# ATmega_lightSensor_blink.net
KiCad netlist of a schematic drawn in EasyEDA
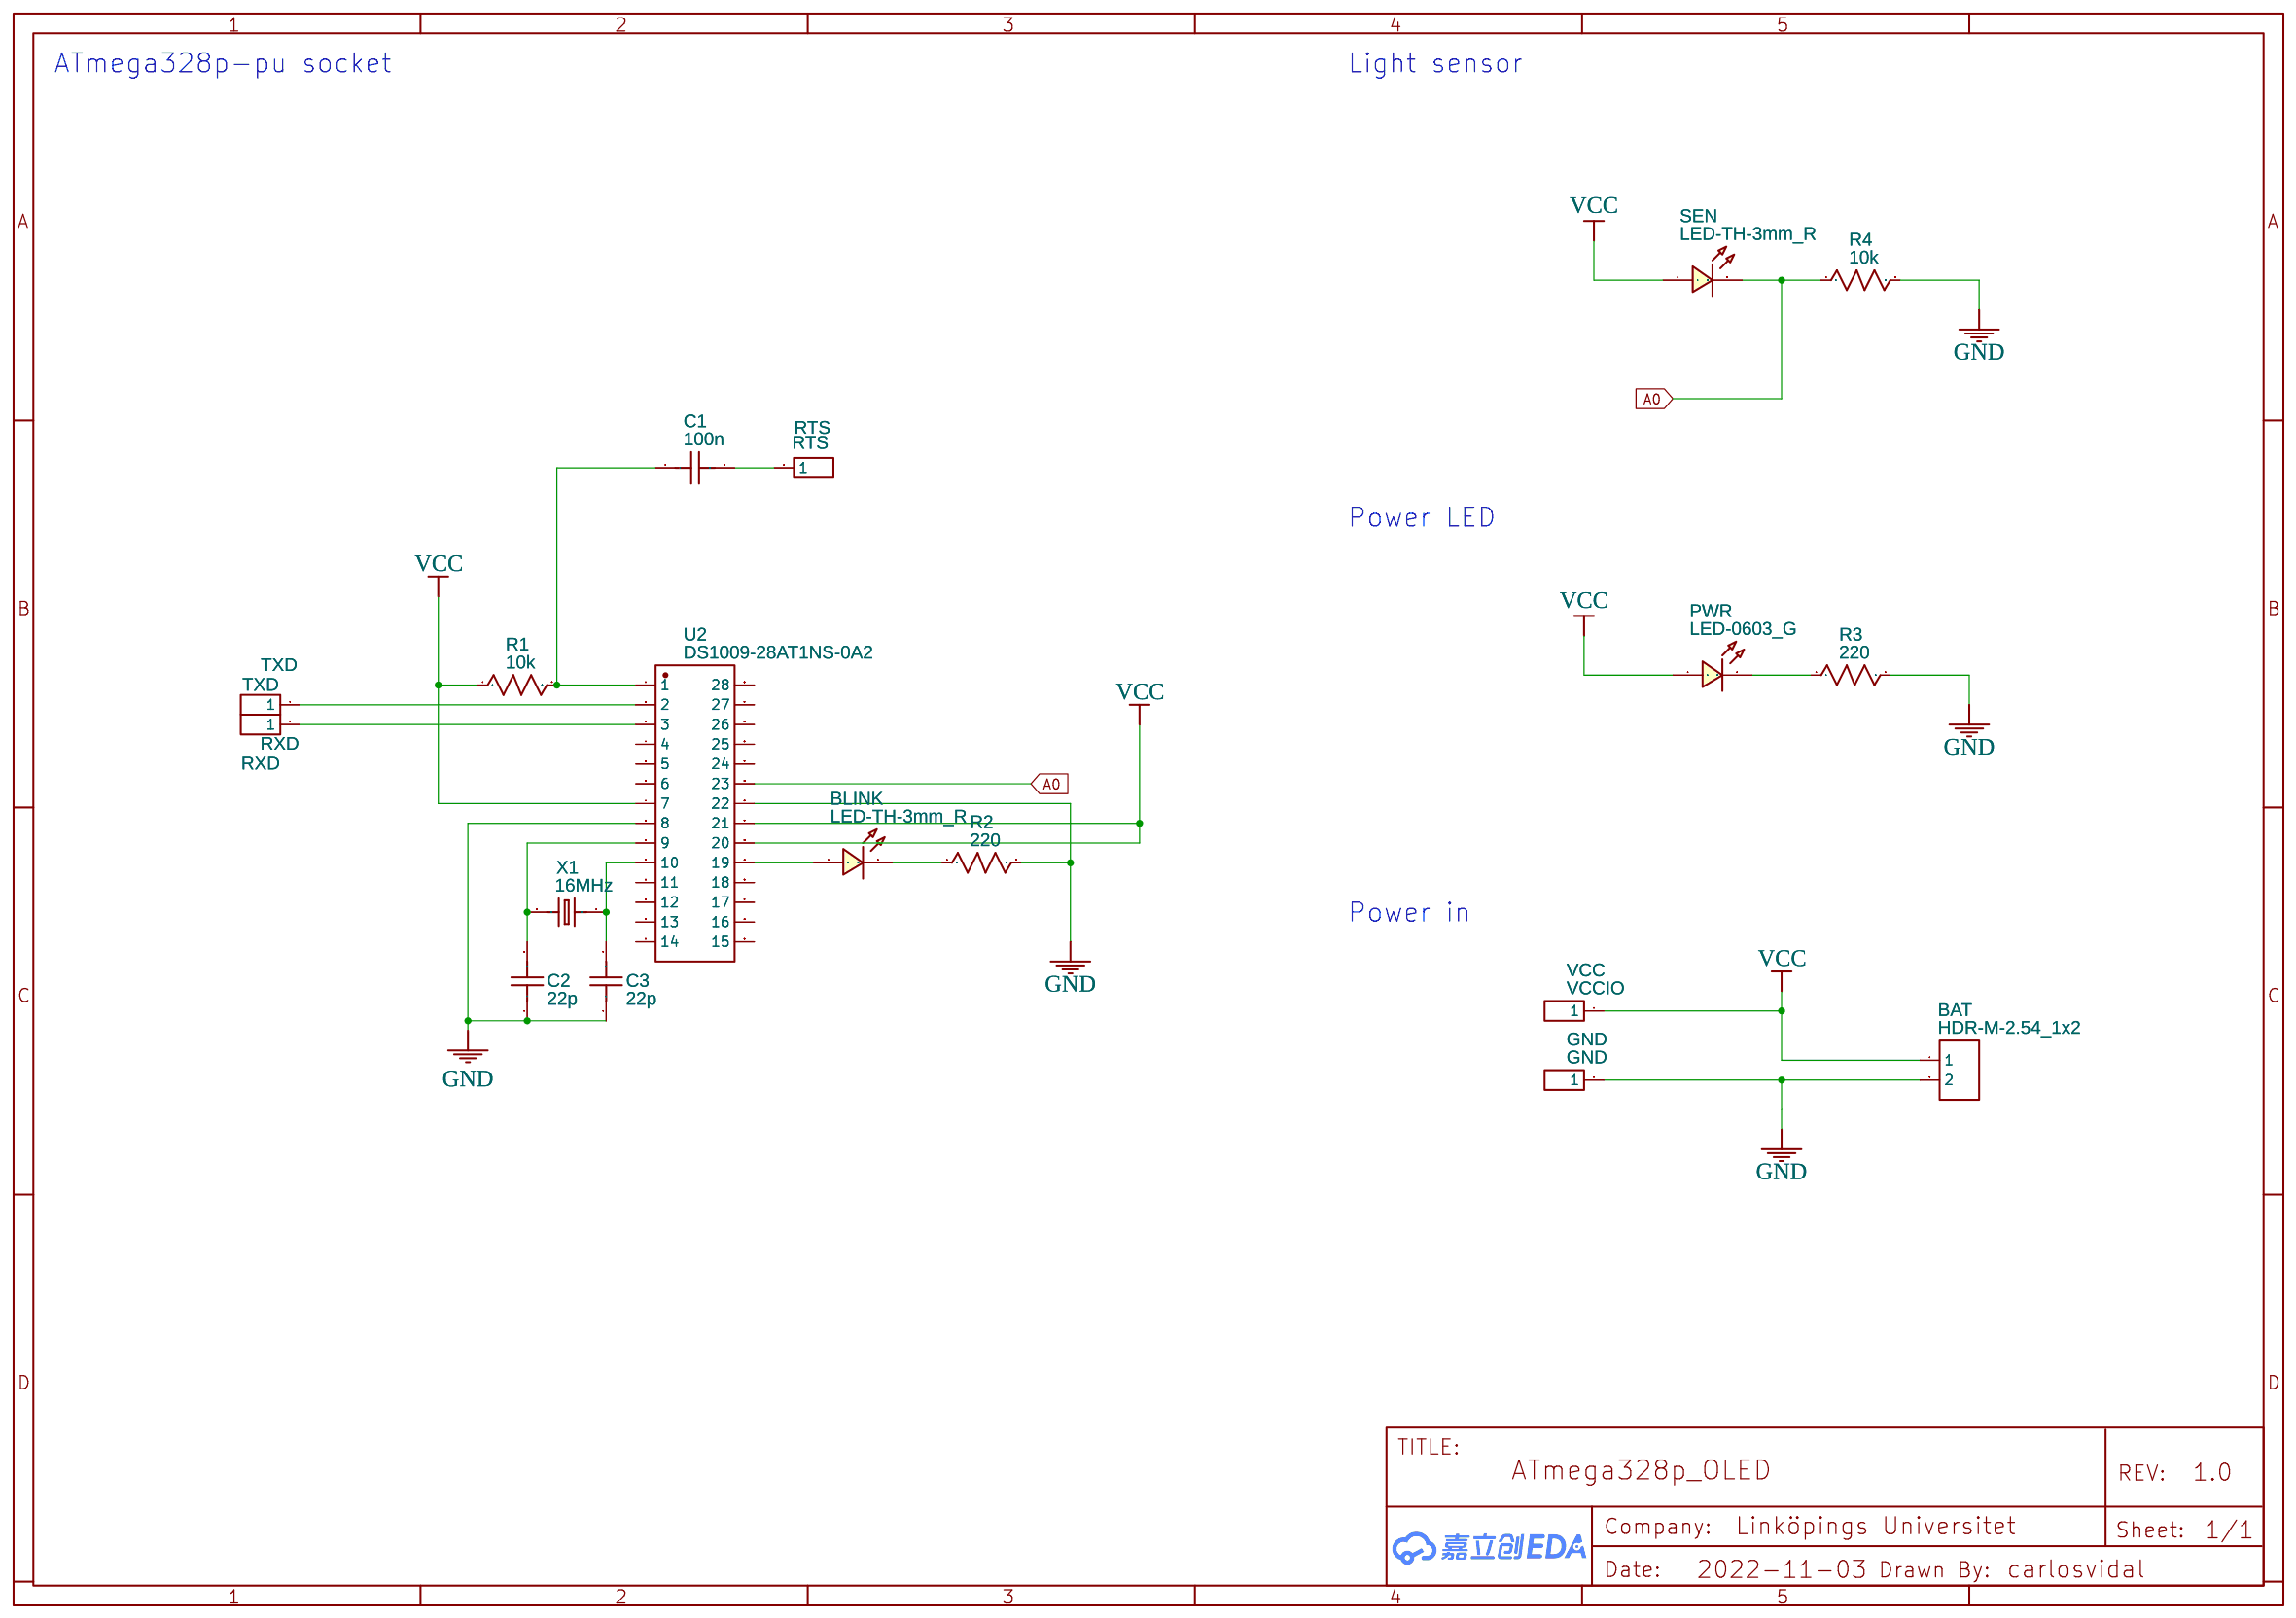
[diagram p0: schematic sheet]

(export (version "E")
  (design (tool "Eeschema 10.0.6"))
  (components
    (comp (ref "BAT") (value "HDR-M-2.54_1x2") (libsource (lib "") (part "HDR-M-2.54_1x2")))
    (comp (ref "BLINK")
      (value "LED-TH-3mm_R")
      (fields
        (field (name "Manufacturer Part") "204-10SDRD/S530-A3-L")
        (field (name "Manufacturer") "EVERLIGHT(台湾亿光)")
      )
      (libsource (lib "") (part "LED-TH-3mm_R"))
    )
    (comp (ref "C1") (value "100n") (libsource (lib "") (part "C_0603_US_1")))
    (comp (ref "C2") (value "22p") (libsource (lib "") (part "C_0603_US")))
    (comp (ref "C3") (value "22p") (libsource (lib "") (part "C_0603_US")))
    (comp (ref "GND") (value "GND") (libsource (lib "") (part "HDR-M-2.54_1x1")))
    (comp (ref "PWR")
      (value "LED-0603_G")
      (fields
        (field (name "Manufacturer Part") "19-217/GHC-YR1S2/3T")
        (field (name "Manufacturer") "EVERLIGHT(台湾亿光)")
      )
      (libsource (lib "") (part "LED-0603_G"))
    )
    (comp (ref "R1") (value "10k") (libsource (lib "") (part "R_0603_US")))
    (comp (ref "R2") (value "220") (libsource (lib "") (part "R_0603_US")))
    (comp (ref "R3") (value "220") (libsource (lib "") (part "R_0603_US")))
    (comp (ref "R4") (value "10k") (libsource (lib "") (part "R_0603_US")))
    (comp (ref "RTS") (value "RTS") (libsource (lib "") (part "HDR-M-2.54_1x1_1")))
    (comp (ref "RXD") (value "RXD") (libsource (lib "") (part "HDR-M-2.54_1x1_3")))
    (comp (ref "SEN")
      (value "LED-TH-3mm_R")
      (fields
        (field (name "Manufacturer Part") "204-10SDRD/S530-A3-L")
        (field (name "Manufacturer") "EVERLIGHT(台湾亿光)")
      )
      (libsource (lib "") (part "LED-TH-3mm_R_1"))
    )
    (comp (ref "TXD") (value "TXD") (libsource (lib "") (part "HDR-M-2.54_1x1_4")))
    (comp (ref "U2")
      (value "DS1009-28AT1NS-0A2")
      (fields (field (name "Manufacturer") "CONNFLY"))
      (libsource (lib "") (part "DS1009-28AT1NS-0A2"))
    )
    (comp (ref "VCC") (value "VCCIO") (libsource (lib "") (part "HDR-M-2.54_1x1_2")))
    (comp (ref "X1")
      (value "16MHz")
      (fields (field (name "Manufacturer Part") "TAXM16M2GLFBET2T") (field (name "Manufacturer") "TAE(雅晶鑫)"))
      (libsource (lib "") (part "HC-49SM16MHz20pF30ppm"))
    )
  )
  (nets
    (net (code "1") (name "A0") (class "Default")
      (node (ref "R4") (pin "1") (pinfunction "1_1") (pintype "unspecified"))
      (node (ref "SEN") (pin "2") (pinfunction "2_2") (pintype "unspecified"))
      (node (ref "U2") (pin "23") (pinfunction "23_23") (pintype "unspecified"))
    )
    (net (code "2") (name "GND") (class "Default")
      (node (ref "BAT") (pin "2") (pinfunction "2_2") (pintype "unspecified"))
      (node (ref "C2") (pin "1") (pinfunction "1_1") (pintype "unspecified"))
      (node (ref "C3") (pin "1") (pinfunction "1_1") (pintype "unspecified"))
      (node (ref "GND") (pin "1") (pinfunction "1_1") (pintype "input"))
      (node (ref "R2") (pin "2") (pinfunction "2_2") (pintype "unspecified"))
      (node (ref "R3") (pin "2") (pinfunction "2_2") (pintype "unspecified"))
      (node (ref "R4") (pin "2") (pinfunction "2_2") (pintype "unspecified"))
      (node (ref "U2") (pin "22") (pinfunction "22_22") (pintype "unspecified"))
      (node (ref "U2") (pin "8") (pinfunction "8_8") (pintype "unspecified"))
    )
    (net (code "3") (name "Net-(BLINK-Pad1)") (class "Default")
      (node (ref "BLINK") (pin "1") (pinfunction "1_1") (pintype "unspecified"))
      (node (ref "U2") (pin "19") (pinfunction "19_19") (pintype "unspecified"))
    )
    (net (code "4") (name "Net-(BLINK-Pad2)") (class "Default")
      (node (ref "BLINK") (pin "2") (pinfunction "2_2") (pintype "unspecified"))
      (node (ref "R2") (pin "1") (pinfunction "1_1") (pintype "unspecified"))
    )
    (net (code "5") (name "Net-(C1-Pad1)") (class "Default")
      (node (ref "C1") (pin "1") (pinfunction "1_1") (pintype "unspecified"))
      (node (ref "R1") (pin "2") (pinfunction "2_2") (pintype "unspecified"))
      (node (ref "U2") (pin "1") (pinfunction "1_1") (pintype "unspecified"))
    )
    (net (code "6") (name "Net-(C1-Pad2)") (class "Default")
      (node (ref "C1") (pin "2") (pinfunction "2_2") (pintype "unspecified"))
      (node (ref "RTS") (pin "1") (pinfunction "1_1") (pintype "input"))
    )
    (net (code "7") (name "Net-(C2-Pad2)") (class "Default")
      (node (ref "C2") (pin "2") (pinfunction "2_2") (pintype "unspecified"))
      (node (ref "U2") (pin "9") (pinfunction "9_9") (pintype "unspecified"))
      (node (ref "X1") (pin "2") (pinfunction "2_2") (pintype "unspecified"))
    )
    (net (code "8") (name "Net-(C3-Pad2)") (class "Default")
      (node (ref "C3") (pin "2") (pinfunction "2_2") (pintype "unspecified"))
      (node (ref "U2") (pin "10") (pinfunction "10_10") (pintype "unspecified"))
      (node (ref "X1") (pin "1") (pinfunction "1_1") (pintype "unspecified"))
    )
    (net (code "9") (name "Net-(PWR-Pad2)") (class "Default")
      (node (ref "PWR") (pin "2") (pinfunction "2_2") (pintype "unspecified"))
      (node (ref "R3") (pin "1") (pinfunction "1_1") (pintype "unspecified"))
    )
    (net (code "10") (name "Net-(RXD-Pad1)") (class "Default")
      (node (ref "RXD") (pin "1") (pinfunction "1_1") (pintype "input"))
      (node (ref "U2") (pin "3") (pinfunction "3_3") (pintype "unspecified"))
    )
    (net (code "11") (name "Net-(TXD-Pad1)") (class "Default")
      (node (ref "TXD") (pin "1") (pinfunction "1_1") (pintype "input"))
      (node (ref "U2") (pin "2") (pinfunction "2_2") (pintype "unspecified"))
    )
    (net (code "12") (name "VCC") (class "Default")
      (node (ref "BAT") (pin "1") (pinfunction "1_1") (pintype "unspecified"))
      (node (ref "PWR") (pin "1") (pinfunction "1_1") (pintype "unspecified"))
      (node (ref "R1") (pin "1") (pinfunction "1_1") (pintype "unspecified"))
      (node (ref "SEN") (pin "1") (pinfunction "1_1") (pintype "unspecified"))
      (node (ref "U2") (pin "20") (pinfunction "20_20") (pintype "unspecified"))
      (node (ref "U2") (pin "21") (pinfunction "21_21") (pintype "unspecified"))
      (node (ref "U2") (pin "7") (pinfunction "7_7") (pintype "unspecified"))
      (node (ref "VCC") (pin "1") (pinfunction "1_1") (pintype "input"))
    )
    (net (code "13") (name "unconnected-(U2-Pad4)") (class "Default")
      (node (ref "U2") (pin "4") (pinfunction "4_4") (pintype "unspecified"))
    )
    (net (code "14") (name "unconnected-(U2-Pad5)") (class "Default")
      (node (ref "U2") (pin "5") (pinfunction "5_5") (pintype "unspecified"))
    )
    (net (code "15") (name "unconnected-(U2-Pad6)") (class "Default")
      (node (ref "U2") (pin "6") (pinfunction "6_6") (pintype "unspecified"))
    )
    (net (code "16") (name "unconnected-(U2-Pad11)") (class "Default")
      (node (ref "U2") (pin "11") (pinfunction "11_11") (pintype "unspecified"))
    )
    (net (code "17") (name "unconnected-(U2-Pad12)") (class "Default")
      (node (ref "U2") (pin "12") (pinfunction "12_12") (pintype "unspecified"))
    )
    (net (code "18") (name "unconnected-(U2-Pad13)") (class "Default")
      (node (ref "U2") (pin "13") (pinfunction "13_13") (pintype "unspecified"))
    )
    (net (code "19") (name "unconnected-(U2-Pad14)") (class "Default")
      (node (ref "U2") (pin "14") (pinfunction "14_14") (pintype "unspecified"))
    )
    (net (code "20") (name "unconnected-(U2-Pad15)") (class "Default")
      (node (ref "U2") (pin "15") (pinfunction "15_15") (pintype "unspecified"))
    )
    (net (code "21") (name "unconnected-(U2-Pad16)") (class "Default")
      (node (ref "U2") (pin "16") (pinfunction "16_16") (pintype "unspecified"))
    )
    (net (code "22") (name "unconnected-(U2-Pad17)") (class "Default")
      (node (ref "U2") (pin "17") (pinfunction "17_17") (pintype "unspecified"))
    )
    (net (code "23") (name "unconnected-(U2-Pad18)") (class "Default")
      (node (ref "U2") (pin "18") (pinfunction "18_18") (pintype "unspecified"))
    )
    (net (code "24") (name "unconnected-(U2-Pad24)") (class "Default")
      (node (ref "U2") (pin "24") (pinfunction "24_24") (pintype "unspecified"))
    )
    (net (code "25") (name "unconnected-(U2-Pad25)") (class "Default")
      (node (ref "U2") (pin "25") (pinfunction "25_25") (pintype "unspecified"))
    )
    (net (code "26") (name "unconnected-(U2-Pad26)") (class "Default")
      (node (ref "U2") (pin "26") (pinfunction "26_26") (pintype "unspecified"))
    )
    (net (code "27") (name "unconnected-(U2-Pad27)") (class "Default")
      (node (ref "U2") (pin "27") (pinfunction "27_27") (pintype "unspecified"))
    )
    (net (code "28") (name "unconnected-(U2-Pad28)") (class "Default")
      (node (ref "U2") (pin "28") (pinfunction "28_28") (pintype "unspecified"))
    )
  )
)
